# Mic-Breakout_v11.net
KiCad netlist of a schematic drawn in EAGLE
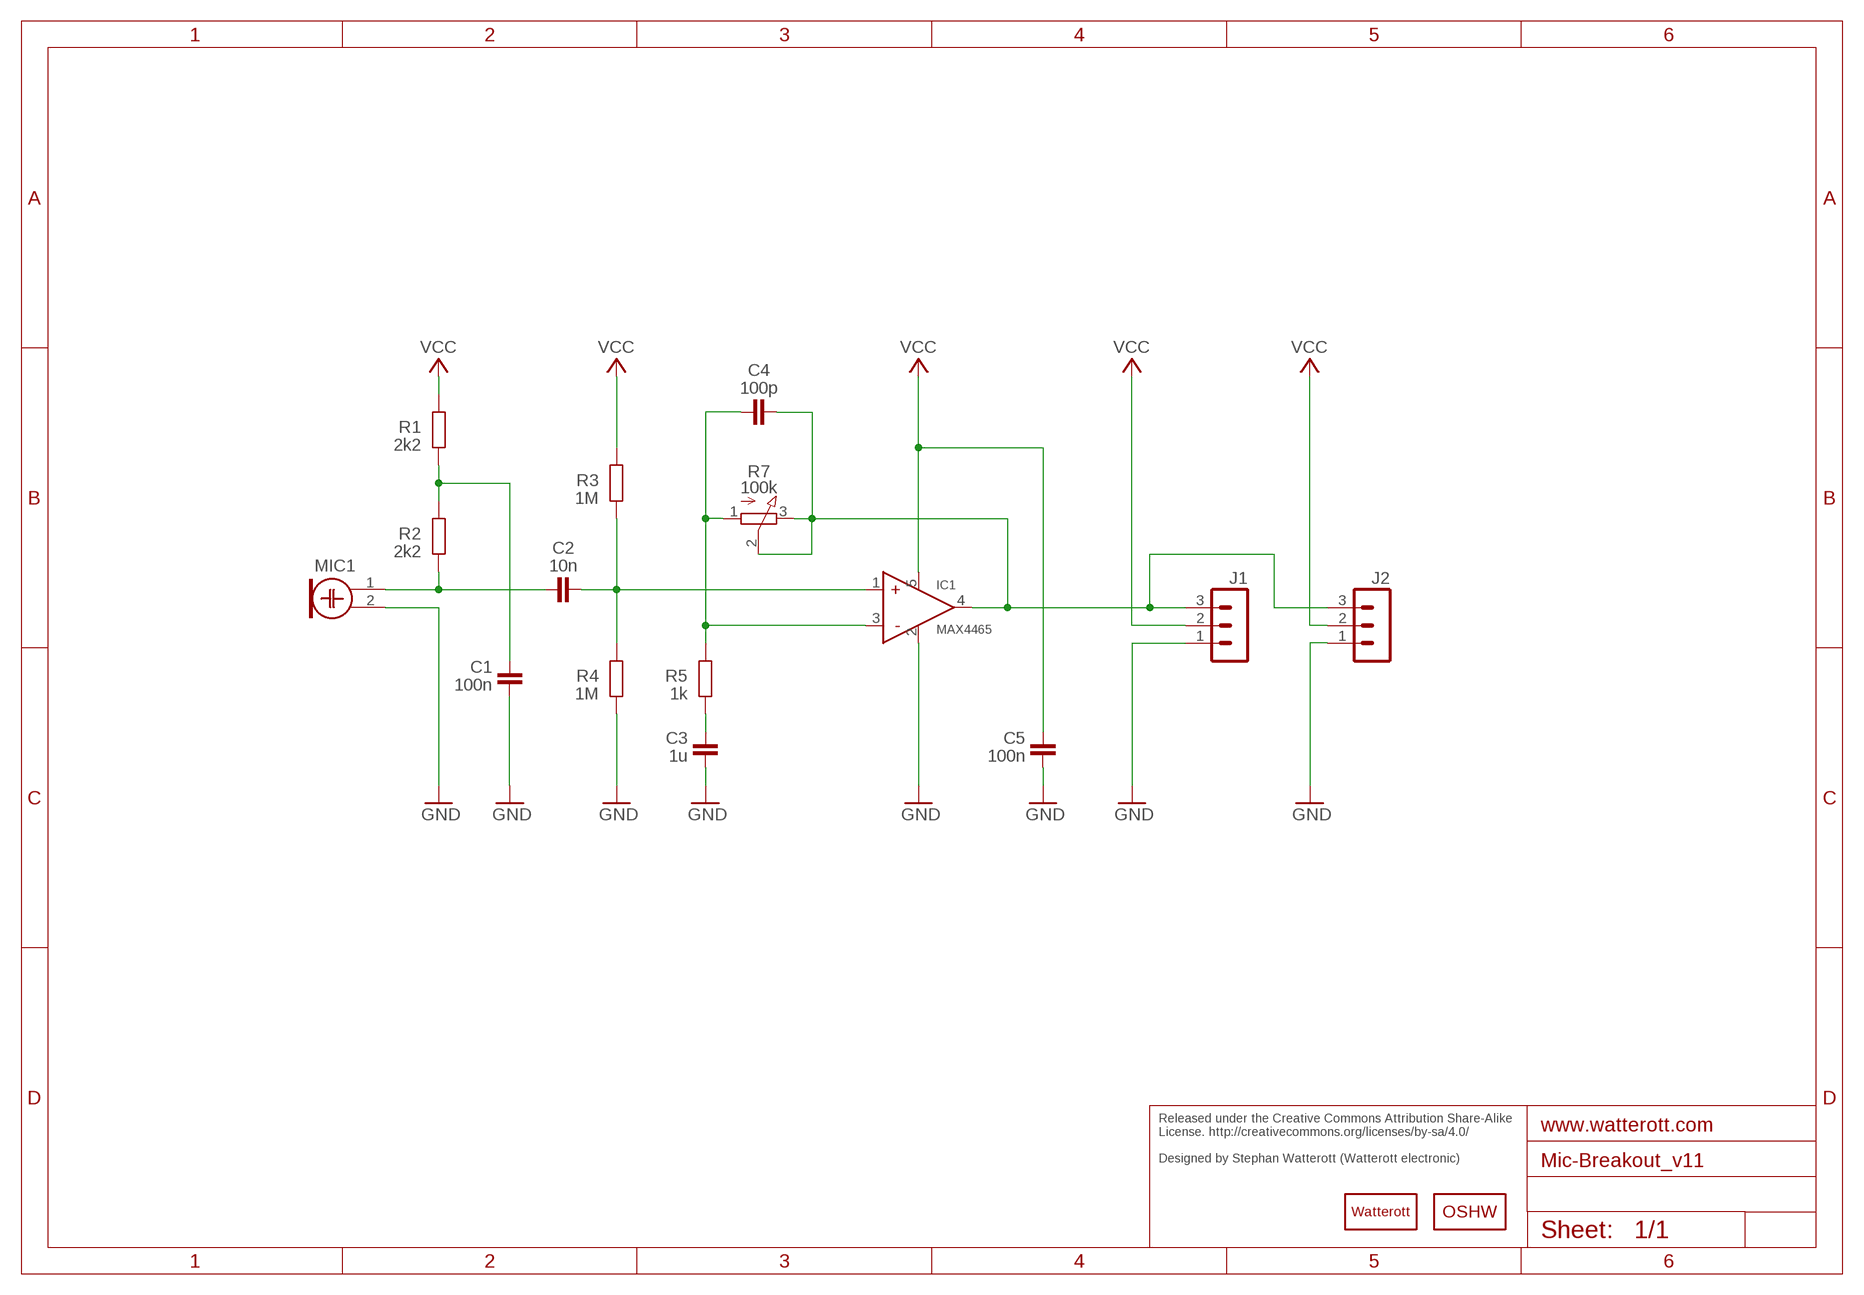
[diagram p0: schematic, sheet 1]

(export (version "E")
  (design (tool "Eeschema 10.0.6"))
  (components
    (comp (ref "C1")
      (value "100n")
      (footprint "eagle-import:C0402")
      (libsource (lib "eagle-import") (part "CAPACITOR-0402"))
    )
    (comp (ref "C2")
      (value "10n")
      (footprint "eagle-import:C0402")
      (libsource (lib "eagle-import") (part "CAPACITOR-0402"))
    )
    (comp (ref "C3")
      (value "1u")
      (footprint "eagle-import:C0402")
      (libsource (lib "eagle-import") (part "CAPACITOR-0402"))
    )
    (comp (ref "C4")
      (value "100p")
      (footprint "eagle-import:C0402")
      (libsource (lib "eagle-import") (part "CAPACITOR-0402"))
    )
    (comp (ref "C5")
      (value "100n")
      (footprint "eagle-import:C0402")
      (libsource (lib "eagle-import") (part "CAPACITOR-0402"))
    )
    (comp (ref "IC1")
      (value "MAX4465")
      (footprint "eagle-import:SOT353")
      (libsource (lib "eagle-import") (part "MAX4465"))
    )
    (comp (ref "J1")
      (value "MA03-1")
      (footprint "eagle-import:MA03-1")
      (libsource (lib "eagle-import") (part "MA03-1"))
    )
    (comp (ref "J2")
      (value "JST_PH_3S3B-PH-SM4-TB")
      (footprint "eagle-import:JST_S3B-PH-SM4-TB")
      (libsource (lib "eagle-import") (part "JST_PH_3S3B-PH-SM4-TB"))
    )
    (comp (ref "LOGO1")
      (value "LOGO-S_PLACE_M")
      (footprint "eagle-import:SPARK_TPLACE_M")
      (libsource (lib "eagle-import") (part "LOGO-S_PLACE_M"))
    )
    (comp (ref "LOGO2")
      (value "OSHW_LOGOX0100")
      (footprint "eagle-import:OSHW_6X100")
      (libsource (lib "eagle-import") (part "OSHW_LOGOX0100"))
    )
    (comp (ref "MIC1")
      (value "CMA-4544PF")
      (footprint "eagle-import:CMA-4544PF")
      (libsource (lib "eagle-import") (part "CMA-4544PF"))
    )
    (comp (ref "R1")
      (value "2k2")
      (footprint "eagle-import:C0402")
      (libsource (lib "eagle-import") (part "RESISTOR-0402"))
    )
    (comp (ref "R2")
      (value "2k2")
      (footprint "eagle-import:C0402")
      (libsource (lib "eagle-import") (part "RESISTOR-0402"))
    )
    (comp (ref "R3")
      (value "1M")
      (footprint "eagle-import:C0402")
      (libsource (lib "eagle-import") (part "RESISTOR-0402"))
    )
    (comp (ref "R4")
      (value "1M")
      (footprint "eagle-import:C0402")
      (libsource (lib "eagle-import") (part "RESISTOR-0402"))
    )
    (comp (ref "R5")
      (value "1k")
      (footprint "eagle-import:C0402")
      (libsource (lib "eagle-import") (part "RESISTOR-0402"))
    )
    (comp (ref "R7")
      (value "100k")
      (footprint "eagle-import:POT_EVM3Y")
      (libsource (lib "eagle-import") (part "POTEVM3Y"))
    )
  )
  (nets
    (net (code "1") (name "GND") (class "Default")
      (node (ref "C1") (pin "1") (pinfunction "1_1") (pintype "passive"))
      (node (ref "C3") (pin "1") (pinfunction "1_1") (pintype "passive"))
      (node (ref "C5") (pin "1") (pinfunction "1_1") (pintype "passive"))
      (node (ref "IC1") (pin "2") (pinfunction "GND_2") (pintype "power_in"))
      (node (ref "J1") (pin "1") (pinfunction "1_1") (pintype "passive"))
      (node (ref "J2") (pin "1") (pinfunction "1_1") (pintype "passive"))
      (node (ref "MIC1") (pin "2") (pinfunction "2_2") (pintype "passive"))
      (node (ref "R4") (pin "1") (pinfunction "1_1") (pintype "passive"))
    )
    (net (code "2") (name "Net-(C1-Pad2)") (class "Default")
      (node (ref "C1") (pin "2") (pinfunction "2_2") (pintype "passive"))
      (node (ref "R1") (pin "1") (pinfunction "1_1") (pintype "passive"))
      (node (ref "R2") (pin "2") (pinfunction "2_2") (pintype "passive"))
    )
    (net (code "3") (name "Net-(C2-Pad1)") (class "Default")
      (node (ref "C2") (pin "1") (pinfunction "1_1") (pintype "passive"))
      (node (ref "MIC1") (pin "1") (pinfunction "1_1") (pintype "passive"))
      (node (ref "R2") (pin "1") (pinfunction "1_1") (pintype "passive"))
    )
    (net (code "4") (name "Net-(C3-Pad2)") (class "Default")
      (node (ref "C3") (pin "2") (pinfunction "2_2") (pintype "passive"))
      (node (ref "R5") (pin "1") (pinfunction "1_1") (pintype "passive"))
    )
    (net (code "5") (name "Net-(IC1-+)") (class "Default")
      (node (ref "C2") (pin "2") (pinfunction "2_2") (pintype "passive"))
      (node (ref "IC1") (pin "1") (pinfunction "+_1") (pintype "input"))
      (node (ref "R3") (pin "1") (pinfunction "1_1") (pintype "passive"))
      (node (ref "R4") (pin "2") (pinfunction "2_2") (pintype "passive"))
    )
    (net (code "6") (name "Net-(IC1--)") (class "Default")
      (node (ref "C4") (pin "2") (pinfunction "2_2") (pintype "passive"))
      (node (ref "IC1") (pin "3") (pinfunction "-_3") (pintype "input"))
      (node (ref "R5") (pin "2") (pinfunction "2_2") (pintype "passive"))
      (node (ref "R7") (pin "1") (pinfunction "A_1") (pintype "passive"))
    )
    (net (code "7") (name "Net-(IC1-OUT)") (class "Default")
      (node (ref "C4") (pin "1") (pinfunction "1_1") (pintype "passive"))
      (node (ref "IC1") (pin "4") (pinfunction "OUT_4") (pintype "output"))
      (node (ref "J1") (pin "3") (pinfunction "3_3") (pintype "passive"))
      (node (ref "J2") (pin "3") (pinfunction "3_3") (pintype "passive"))
      (node (ref "R7") (pin "2") (pinfunction "S_2") (pintype "passive"))
      (node (ref "R7") (pin "3") (pinfunction "E_3") (pintype "passive"))
    )
    (net (code "8") (name "VCC") (class "Default")
      (node (ref "C5") (pin "2") (pinfunction "2_2") (pintype "passive"))
      (node (ref "IC1") (pin "5") (pinfunction "VCC_5") (pintype "power_in"))
      (node (ref "J1") (pin "2") (pinfunction "2_2") (pintype "passive"))
      (node (ref "J2") (pin "2") (pinfunction "2_2") (pintype "passive"))
      (node (ref "R1") (pin "2") (pinfunction "2_2") (pintype "passive"))
      (node (ref "R3") (pin "2") (pinfunction "2_2") (pintype "passive"))
    )
  )
)
